# wheelBLE2_FRAM.net
KiCad netlist of a schematic drawn in EAGLE
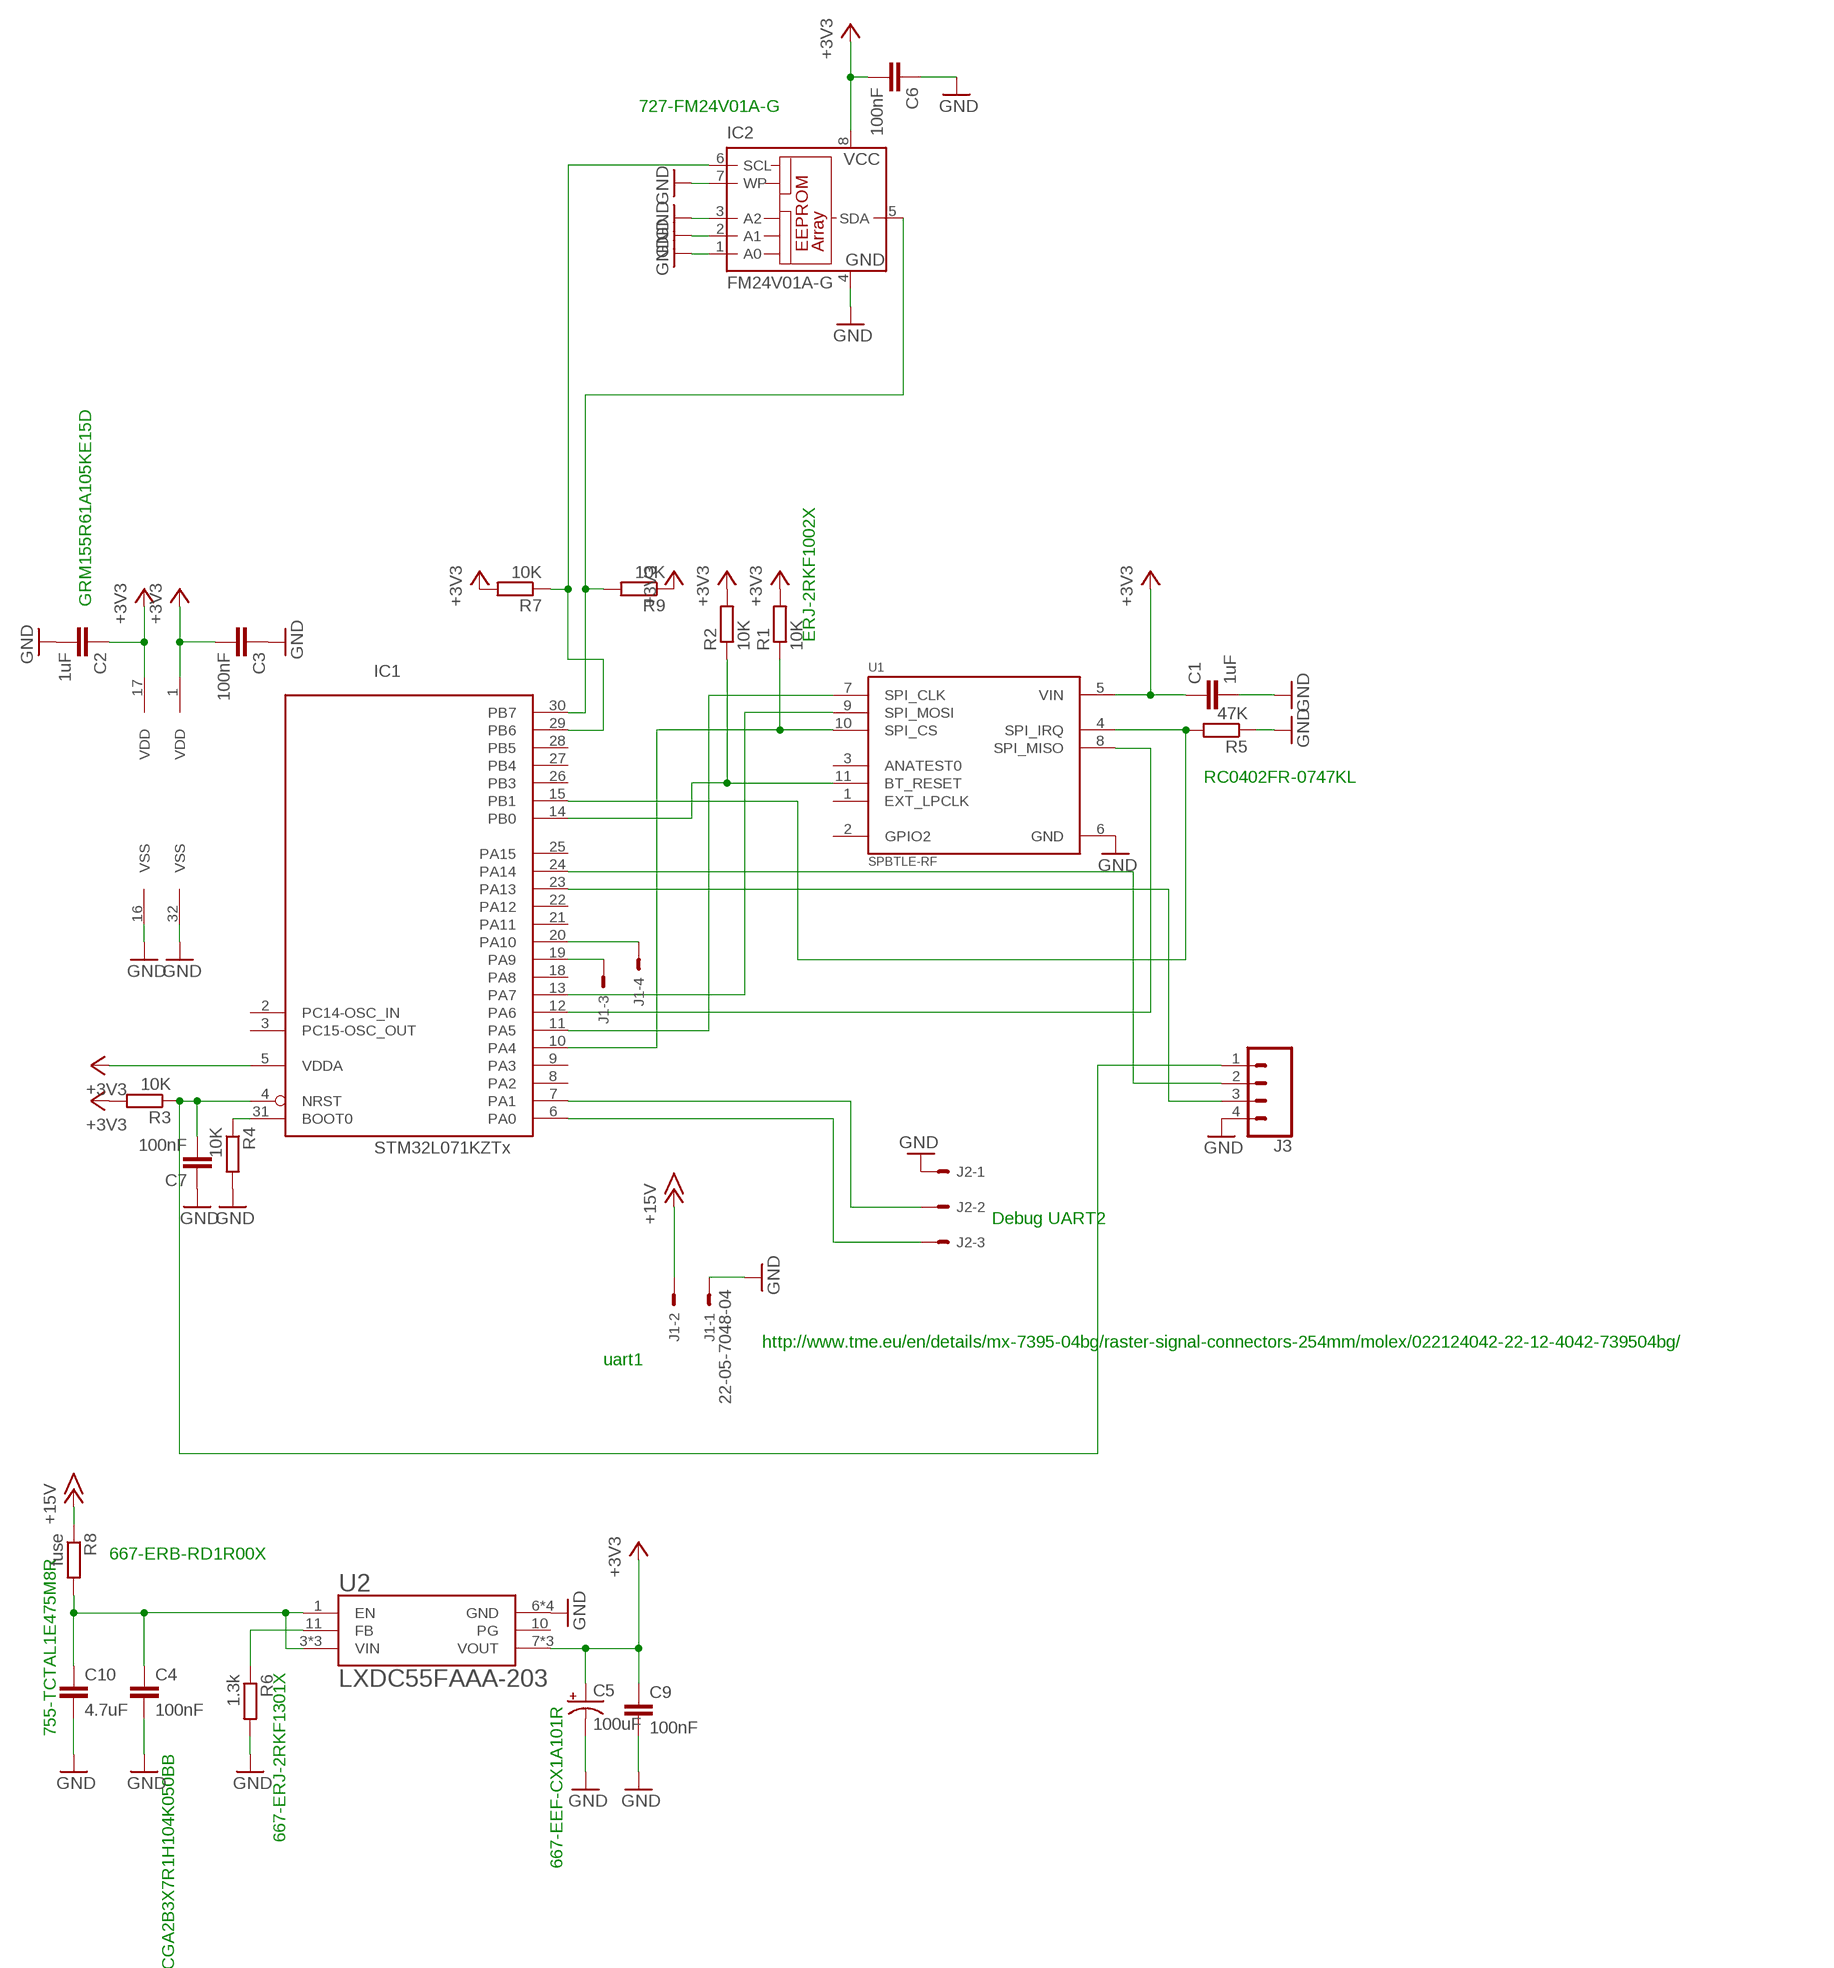
[diagram p0: schematic, sheet 1]

(export (version "E")
  (design (tool "Eeschema 10.0.6"))
  (components
    (comp (ref "C1")
      (value "1uF")
      (footprint "eagle-import:C0402")
      (libsource (lib "eagle-import") (part "C-EUC0402"))
    )
    (comp (ref "C2")
      (value "1uF")
      (footprint "eagle-import:C0402")
      (libsource (lib "eagle-import") (part "C-EUC0402"))
    )
    (comp (ref "C3")
      (value "100nF")
      (footprint "eagle-import:C0402")
      (libsource (lib "eagle-import") (part "C-EUC0402"))
    )
    (comp (ref "C4")
      (value "100nF")
      (footprint "eagle-import:C0402")
      (libsource (lib "eagle-import") (part "C-EUC0402"))
    )
    (comp (ref "C5")
      (value "100uF")
      (footprint "eagle-import:EIA7343")
      (libsource (lib "eagle-import") (part "100UF-POLAR-EIA7343-10V-10%(TANT)"))
    )
    (comp (ref "C6")
      (value "100nF")
      (footprint "eagle-import:C0402")
      (libsource (lib "eagle-import") (part "C-EUC0402"))
    )
    (comp (ref "C7")
      (value "100nF")
      (footprint "eagle-import:C0402")
      (libsource (lib "eagle-import") (part "C-EUC0402"))
    )
    (comp (ref "C9")
      (value "100nF")
      (footprint "eagle-import:C0402")
      (libsource (lib "eagle-import") (part "C-EUC0402"))
    )
    (comp (ref "C10")
      (value "4.7uF")
      (footprint "eagle-import:1206")
      (libsource (lib "eagle-import") (part "4.7UF-1206-16V-(+80/-20%)"))
    )
    (comp (ref "IC1")
      (value "STM32L071KZTx")
      (footprint "eagle-import:LQFP32")
      (libsource (lib "eagle-import") (part "STM32L051KT8"))
    )
    (comp (ref "IC2")
      (value "FM24V01A-G")
      (footprint "eagle-import:SO-08M")
      (fields (field (name "MF") "RAMTRON INTERNATIONAL CORP") (field (name "MPN") "FM24C64-S"))
      (libsource (lib "eagle-import") (part "24SMC64"))
    )
    (comp (ref "J1")
      (value "22-05-7048-04")
      (footprint "eagle-import:7395-04")
      (libsource (lib "eagle-import") (part "22-?-0405-7048"))
    )
    (comp (ref "J2")
      (value "22-05-7038-03")
      (footprint "eagle-import:7395-03")
      (libsource (lib "eagle-import") (part "22-?-0305-7038"))
    )
    (comp (ref "J3")
      (value "CONN_04")
      (footprint "eagle-import:1X04")
      (libsource (lib "eagle-import") (part "CONN_04"))
    )
    (comp (ref "R1")
      (value "10K")
      (footprint "eagle-import:R0402")
      (libsource (lib "eagle-import") (part "R-EU_R0402"))
    )
    (comp (ref "R2")
      (value "10K")
      (footprint "eagle-import:R0402")
      (libsource (lib "eagle-import") (part "R-EU_R0402"))
    )
    (comp (ref "R3")
      (value "10K")
      (footprint "eagle-import:R0402")
      (libsource (lib "eagle-import") (part "R-EU_R0402"))
    )
    (comp (ref "R4")
      (value "10K")
      (footprint "eagle-import:R0402")
      (libsource (lib "eagle-import") (part "R-EU_R0402"))
    )
    (comp (ref "R5")
      (value "47K")
      (footprint "eagle-import:R0402")
      (libsource (lib "eagle-import") (part "R-EU_R0402"))
    )
    (comp (ref "R6")
      (value "1.3k")
      (footprint "eagle-import:R0402")
      (libsource (lib "eagle-import") (part "R-EU_R0402"))
    )
    (comp (ref "R7")
      (value "10K")
      (footprint "eagle-import:R0402")
      (libsource (lib "eagle-import") (part "R-EU_R0402"))
    )
    (comp (ref "R8")
      (value "fuse")
      (footprint "eagle-import:R0402")
      (libsource (lib "eagle-import") (part "R-EU_R0402"))
    )
    (comp (ref "R9")
      (value "10K")
      (footprint "eagle-import:R0402")
      (libsource (lib "eagle-import") (part "R-EU_R0402"))
    )
    (comp (ref "U1")
      (value "SPBTLE-RF")
      (footprint "eagle-import:XCVR_SPBTLE-RF")
      (fields (field (name "MF") "STMicroelectronics"))
      (libsource (lib "eagle-import") (part "SPBTLE-RF"))
    )
    (comp (ref "U2")
      (value "LXDC55FAAA-203")
      (footprint "eagle-import:CONV_LXDC55FAAA-203")
      (fields (field (name "MF") "Murata"))
      (libsource (lib "eagle-import") (part "LXDC55FAAA-203"))
    )
  )
  (nets
    (net (code "1") (name "+3V3") (class "Default")
      (node (ref "C1") (pin "1") (pinfunction "1_1") (pintype "passive"))
      (node (ref "C2") (pin "1") (pinfunction "1_1") (pintype "passive"))
      (node (ref "C3") (pin "2") (pinfunction "2_2") (pintype "passive"))
      (node (ref "C5") (pin "A") (pinfunction "+_A") (pintype "passive"))
      (node (ref "C6") (pin "2") (pinfunction "2_2") (pintype "passive"))
      (node (ref "C9") (pin "1") (pinfunction "1_1") (pintype "passive"))
      (node (ref "IC1") (pin "1") (pinfunction "VDD_1") (pintype "power_in"))
      (node (ref "IC1") (pin "17") (pinfunction "VDD_17") (pintype "power_in"))
      (node (ref "IC1") (pin "5") (pinfunction "VDDA_5") (pintype "power_in"))
      (node (ref "IC2") (pin "8") (pinfunction "VCC_8") (pintype "power_in"))
      (node (ref "R1") (pin "2") (pinfunction "2_2") (pintype "passive"))
      (node (ref "R2") (pin "2") (pinfunction "2_2") (pintype "passive"))
      (node (ref "R3") (pin "2") (pinfunction "2_2") (pintype "passive"))
      (node (ref "R7") (pin "2") (pinfunction "2_2") (pintype "passive"))
      (node (ref "R9") (pin "1") (pinfunction "1_1") (pintype "passive"))
      (node (ref "U1") (pin "5") (pinfunction "VIN_5") (pintype "power_in"))
      (node (ref "U2") (pin "7") (pinfunction "VOUT_7") (pintype "output"))
      (node (ref "U2") (pin "8") (pinfunction "VOUT_8") (pintype "output"))
      (node (ref "U2") (pin "9") (pinfunction "VOUT_9") (pintype "output"))
    )
    (net (code "2") (name "+15V") (class "Default")
      (node (ref "J1") (pin "2") (pinfunction "S_2") (pintype "passive"))
      (node (ref "R8") (pin "1") (pinfunction "1_1") (pintype "passive"))
    )
    (net (code "3") (name "GND") (class "Default")
      (node (ref "C1") (pin "2") (pinfunction "2_2") (pintype "passive"))
      (node (ref "C10") (pin "2") (pinfunction "2_2") (pintype "passive"))
      (node (ref "C2") (pin "2") (pinfunction "2_2") (pintype "passive"))
      (node (ref "C3") (pin "1") (pinfunction "1_1") (pintype "passive"))
      (node (ref "C4") (pin "2") (pinfunction "2_2") (pintype "passive"))
      (node (ref "C5") (pin "C") (pinfunction "-_C") (pintype "passive"))
      (node (ref "C6") (pin "1") (pinfunction "1_1") (pintype "passive"))
      (node (ref "C7") (pin "1") (pinfunction "1_1") (pintype "passive"))
      (node (ref "C9") (pin "2") (pinfunction "2_2") (pintype "passive"))
      (node (ref "IC1") (pin "16") (pinfunction "VSS_16") (pintype "power_in"))
      (node (ref "IC1") (pin "32") (pinfunction "VSS_32") (pintype "power_in"))
      (node (ref "IC2") (pin "1") (pinfunction "A0_1") (pintype "input"))
      (node (ref "IC2") (pin "2") (pinfunction "A1_2") (pintype "input"))
      (node (ref "IC2") (pin "3") (pinfunction "A2_3") (pintype "input"))
      (node (ref "IC2") (pin "4") (pinfunction "GND_4") (pintype "power_in"))
      (node (ref "IC2") (pin "7") (pinfunction "WP_7") (pintype "input"))
      (node (ref "J1") (pin "1") (pinfunction "S_1") (pintype "passive"))
      (node (ref "J2") (pin "1") (pinfunction "S_1") (pintype "passive"))
      (node (ref "J3") (pin "4") (pinfunction "4_4") (pintype "passive"))
      (node (ref "R4") (pin "2") (pinfunction "2_2") (pintype "passive"))
      (node (ref "R5") (pin "1") (pinfunction "1_1") (pintype "passive"))
      (node (ref "R6") (pin "2") (pinfunction "2_2") (pintype "passive"))
      (node (ref "U1") (pin "6") (pinfunction "GND_6") (pintype "power_in"))
      (node (ref "U2") (pin "12") (pinfunction "GND_12") (pintype "power_in"))
      (node (ref "U2") (pin "13") (pinfunction "GND_13") (pintype "power_in"))
      (node (ref "U2") (pin "14") (pinfunction "GND_14") (pintype "power_in"))
      (node (ref "U2") (pin "6") (pinfunction "GND_6") (pintype "power_in"))
    )
    (net (code "4") (name "Net-(IC1A-BOOT0)") (class "Default")
      (node (ref "IC1") (pin "31") (pinfunction "BOOT0_31") (pintype "input"))
      (node (ref "R4") (pin "1") (pinfunction "1_1") (pintype "passive"))
    )
    (net (code "5") (name "Net-(IC1A-NRST)") (class "Default")
      (node (ref "C7") (pin "2") (pinfunction "2_2") (pintype "passive"))
      (node (ref "IC1") (pin "4") (pinfunction "NRST_4") (pintype "bidirectional"))
      (node (ref "J3") (pin "1") (pinfunction "1_1") (pintype "passive"))
      (node (ref "R3") (pin "1") (pinfunction "1_1") (pintype "passive"))
    )
    (net (code "6") (name "Net-(IC1A-PA0)") (class "Default")
      (node (ref "IC1") (pin "6") (pinfunction "PA0_6") (pintype "bidirectional"))
      (node (ref "J2") (pin "3") (pinfunction "S_3") (pintype "passive"))
    )
    (net (code "7") (name "Net-(IC1A-PA1)") (class "Default")
      (node (ref "IC1") (pin "7") (pinfunction "PA1_7") (pintype "bidirectional"))
      (node (ref "J2") (pin "2") (pinfunction "S_2") (pintype "passive"))
    )
    (net (code "8") (name "Net-(IC1A-PA4)") (class "Default")
      (node (ref "IC1") (pin "10") (pinfunction "PA4_10") (pintype "bidirectional"))
      (node (ref "R1") (pin "1") (pinfunction "1_1") (pintype "passive"))
      (node (ref "U1") (pin "10") (pinfunction "SPI_CS_10") (pintype "input"))
    )
    (net (code "9") (name "Net-(IC1A-PA5)") (class "Default")
      (node (ref "IC1") (pin "11") (pinfunction "PA5_11") (pintype "bidirectional"))
      (node (ref "U1") (pin "7") (pinfunction "SPI_CLK_7") (pintype "input"))
    )
    (net (code "10") (name "Net-(IC1A-PA6)") (class "Default")
      (node (ref "IC1") (pin "12") (pinfunction "PA6_12") (pintype "bidirectional"))
      (node (ref "U1") (pin "8") (pinfunction "SPI_MISO_8") (pintype "output"))
    )
    (net (code "11") (name "Net-(IC1A-PA7)") (class "Default")
      (node (ref "IC1") (pin "13") (pinfunction "PA7_13") (pintype "bidirectional"))
      (node (ref "U1") (pin "9") (pinfunction "SPI_MOSI_9") (pintype "input"))
    )
    (net (code "12") (name "Net-(IC1A-PA9)") (class "Default")
      (node (ref "IC1") (pin "19") (pinfunction "PA9_19") (pintype "bidirectional"))
      (node (ref "J1") (pin "3") (pinfunction "S_3") (pintype "passive"))
    )
    (net (code "13") (name "Net-(IC1A-PA10)") (class "Default")
      (node (ref "IC1") (pin "20") (pinfunction "PA10_20") (pintype "bidirectional"))
      (node (ref "J1") (pin "4") (pinfunction "S_4") (pintype "passive"))
    )
    (net (code "14") (name "Net-(IC1A-PA13)") (class "Default")
      (node (ref "IC1") (pin "23") (pinfunction "PA13_23") (pintype "bidirectional"))
      (node (ref "J3") (pin "3") (pinfunction "3_3") (pintype "passive"))
    )
    (net (code "15") (name "Net-(IC1A-PA14)") (class "Default")
      (node (ref "IC1") (pin "24") (pinfunction "PA14_24") (pintype "bidirectional"))
      (node (ref "J3") (pin "2") (pinfunction "2_2") (pintype "passive"))
    )
    (net (code "16") (name "Net-(IC1A-PB0)") (class "Default")
      (node (ref "IC1") (pin "14") (pinfunction "PB0_14") (pintype "bidirectional"))
      (node (ref "R2") (pin "1") (pinfunction "1_1") (pintype "passive"))
      (node (ref "U1") (pin "11") (pinfunction "BT_RESET_11") (pintype "input"))
    )
    (net (code "17") (name "Net-(IC1A-PB1)") (class "Default")
      (node (ref "IC1") (pin "15") (pinfunction "PB1_15") (pintype "bidirectional"))
      (node (ref "R5") (pin "2") (pinfunction "2_2") (pintype "passive"))
      (node (ref "U1") (pin "4") (pinfunction "SPI_IRQ_4") (pintype "output"))
    )
    (net (code "18") (name "Net-(IC1A-PB6)") (class "Default")
      (node (ref "IC1") (pin "29") (pinfunction "PB6_29") (pintype "bidirectional"))
      (node (ref "IC2") (pin "6") (pinfunction "SCL_6") (pintype "input"))
      (node (ref "R7") (pin "1") (pinfunction "1_1") (pintype "passive"))
    )
    (net (code "19") (name "Net-(IC1A-PB7)") (class "Default")
      (node (ref "IC1") (pin "30") (pinfunction "PB7_30") (pintype "bidirectional"))
      (node (ref "IC2") (pin "5") (pinfunction "SDA_5") (pintype "bidirectional"))
      (node (ref "R9") (pin "2") (pinfunction "2_2") (pintype "passive"))
    )
    (net (code "20") (name "Net-(U2-EN)") (class "Default")
      (node (ref "C10") (pin "1") (pinfunction "1_1") (pintype "passive"))
      (node (ref "C4") (pin "1") (pinfunction "1_1") (pintype "passive"))
      (node (ref "R8") (pin "2") (pinfunction "2_2") (pintype "passive"))
      (node (ref "U2") (pin "1") (pinfunction "EN_1") (pintype "input"))
      (node (ref "U2") (pin "3") (pinfunction "VIN_3") (pintype "input"))
      (node (ref "U2") (pin "4") (pinfunction "VIN_4") (pintype "input"))
      (node (ref "U2") (pin "5") (pinfunction "VIN_5") (pintype "input"))
    )
    (net (code "21") (name "Net-(U2-FB)") (class "Default")
      (node (ref "R6") (pin "1") (pinfunction "1_1") (pintype "passive"))
      (node (ref "U2") (pin "11") (pinfunction "FB_11") (pintype "input"))
    )
    (net (code "22") (name "unconnected-(IC1A-PA2-Pad8)") (class "Default")
      (node (ref "IC1") (pin "8") (pinfunction "PA2_8") (pintype "bidirectional"))
    )
    (net (code "23") (name "unconnected-(IC1A-PA3-Pad9)") (class "Default")
      (node (ref "IC1") (pin "9") (pinfunction "PA3_9") (pintype "bidirectional"))
    )
    (net (code "24") (name "unconnected-(IC1A-PA8-Pad18)") (class "Default")
      (node (ref "IC1") (pin "18") (pinfunction "PA8_18") (pintype "bidirectional"))
    )
    (net (code "25") (name "unconnected-(IC1A-PA11-Pad21)") (class "Default")
      (node (ref "IC1") (pin "21") (pinfunction "PA11_21") (pintype "bidirectional"))
    )
    (net (code "26") (name "unconnected-(IC1A-PA12-Pad22)") (class "Default")
      (node (ref "IC1") (pin "22") (pinfunction "PA12_22") (pintype "bidirectional"))
    )
    (net (code "27") (name "unconnected-(IC1A-PA15-Pad25)") (class "Default")
      (node (ref "IC1") (pin "25") (pinfunction "PA15_25") (pintype "bidirectional"))
    )
    (net (code "28") (name "unconnected-(IC1A-PB3-Pad26)") (class "Default")
      (node (ref "IC1") (pin "26") (pinfunction "PB3_26") (pintype "bidirectional"))
    )
    (net (code "29") (name "unconnected-(IC1A-PB4-Pad27)") (class "Default")
      (node (ref "IC1") (pin "27") (pinfunction "PB4_27") (pintype "bidirectional"))
    )
    (net (code "30") (name "unconnected-(IC1A-PB5-Pad28)") (class "Default")
      (node (ref "IC1") (pin "28") (pinfunction "PB5_28") (pintype "bidirectional"))
    )
    (net (code "31") (name "unconnected-(IC1A-PC14-OSC_IN-Pad2)") (class "Default")
      (node (ref "IC1") (pin "2") (pinfunction "PC14-OSC_IN_2") (pintype "bidirectional"))
    )
    (net (code "32") (name "unconnected-(IC1A-PC15-OSC_OUT-Pad3)") (class "Default")
      (node (ref "IC1") (pin "3") (pinfunction "PC15-OSC_OUT_3") (pintype "bidirectional"))
    )
    (net (code "33") (name "unconnected-(U1-ANATEST0-Pad3)") (class "Default")
      (node (ref "U1") (pin "3") (pinfunction "ANATEST0_3") (pintype "input"))
    )
    (net (code "34") (name "unconnected-(U1-EXT_LPCLK-Pad1)") (class "Default")
      (node (ref "U1") (pin "1") (pinfunction "EXT_LPCLK_1") (pintype "input"))
    )
    (net (code "35") (name "unconnected-(U1-GPIO2-Pad2)") (class "Default")
      (node (ref "U1") (pin "2") (pinfunction "GPIO2_2") (pintype "bidirectional"))
    )
    (net (code "36") (name "unconnected-(U2-PG-Pad10)") (class "Default")
      (node (ref "U2") (pin "10") (pinfunction "PG_10") (pintype "output"))
    )
  )
)
